# BM2Step_V1_0.net
KiCad netlist of a schematic drawn in EAGLE
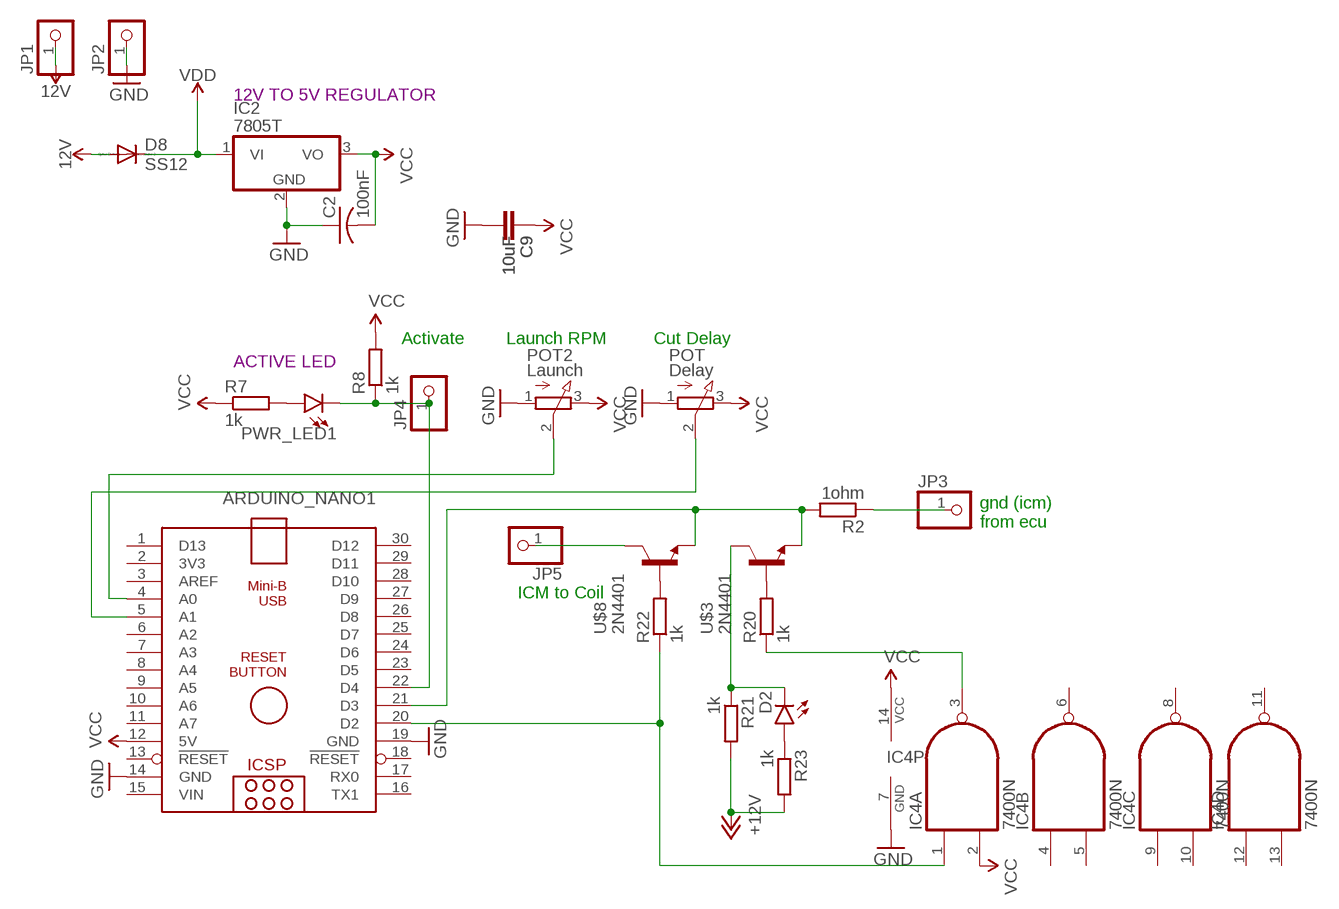
[diagram p0: schematic, sheet 1]

(export (version "E")
  (design (tool "Eeschema 10.0.6"))
  (components
    (comp (ref "ARDUINO_NANO1")
      (value "ARDUINO_NANO")
      (footprint "eagle-import:ARDUINO_NANO")
      (libsource (lib "eagle-import") (part "ARDUINO_NANO"))
    )
    (comp (ref "C2")
      (value "100nF")
      (footprint "eagle-import:C025-024X044")
      (libsource (lib "eagle-import") (part "C-US025-024X044"))
    )
    (comp (ref "C9")
      (value "10uF")
      (footprint "eagle-import:AXIAL-5MM")
      (libsource (lib "eagle-import") (part "CAP_"))
    )
    (comp (ref "D2")
      (value "LED3MM")
      (footprint "eagle-import:LED3MM")
      (libsource (lib "eagle-import") (part "led_259_LED3MM"))
    )
    (comp (ref "D8")
      (value "SS12")
      (footprint "eagle-import:D-7.5")
      (libsource (lib "eagle-import") (part "DIODE-D-7.5"))
    )
    (comp (ref "IC2")
      (value "7805T")
      (footprint "eagle-import:TO220H")
      (libsource (lib "eagle-import") (part "78T05"))
    )
    (comp (ref "IC4")
      (value "7400N")
      (footprint "eagle-import:DIL14")
      (libsource (lib "eagle-import") (part "7400N"))
    )
    (comp (ref "JP1")
      (value "PINHD-1X1_LARGE")
      (footprint "eagle-import:1X01_LARGE")
      (libsource (lib "eagle-import") (part "PINHD-1X1_LARGE"))
    )
    (comp (ref "JP2")
      (value "PINHD-1X1_LARGE")
      (footprint "eagle-import:1X01_LARGE")
      (libsource (lib "eagle-import") (part "PINHD-1X1_LARGE"))
    )
    (comp (ref "JP3")
      (value "PINHD-1X1_LARGE")
      (footprint "eagle-import:1X01_LARGE")
      (libsource (lib "eagle-import") (part "PINHD-1X1_LARGE"))
    )
    (comp (ref "JP4")
      (value "PINHD-1X1_LARGE")
      (footprint "eagle-import:1X01_LARGE")
      (libsource (lib "eagle-import") (part "PINHD-1X1_LARGE"))
    )
    (comp (ref "JP5")
      (value "PINHD-1X1_LARGE")
      (footprint "eagle-import:1X01_LARGE")
      (libsource (lib "eagle-import") (part "PINHD-1X1_LARGE"))
    )
    (comp (ref "POT")
      (value "Delay")
      (footprint "eagle-import:EVUF")
      (libsource (lib "eagle-import") (part "EVUAF2"))
    )
    (comp (ref "POT2")
      (value "Launch")
      (footprint "eagle-import:EVUF")
      (libsource (lib "eagle-import") (part "EVUAF2"))
    )
    (comp (ref "PWR_LED1")
      (value "LED3MM")
      (footprint "eagle-import:LED_3MM")
      (libsource (lib "eagle-import") (part "LED3MM"))
    )
    (comp (ref "R2")
      (value "1ohm")
      (footprint "eagle-import:0204_7")
      (libsource (lib "eagle-import") (part "R-EU_0204/7"))
    )
    (comp (ref "R7")
      (value "1k")
      (footprint "eagle-import:0204_7")
      (libsource (lib "eagle-import") (part "R-EU_0204/7"))
    )
    (comp (ref "R8")
      (value "1k")
      (footprint "eagle-import:0204_7")
      (libsource (lib "eagle-import") (part "R-EU_0204/7"))
    )
    (comp (ref "R20")
      (value "1k")
      (footprint "eagle-import:0204_7")
      (libsource (lib "eagle-import") (part "R-EU_0204/7"))
    )
    (comp (ref "R21")
      (value "1k")
      (footprint "eagle-import:0204_7")
      (libsource (lib "eagle-import") (part "R-EU_0204/7"))
    )
    (comp (ref "R22")
      (value "1k")
      (footprint "eagle-import:0204_7")
      (libsource (lib "eagle-import") (part "R-EU_0204/7"))
    )
    (comp (ref "R23")
      (value "1k")
      (footprint "eagle-import:0204_7")
      (libsource (lib "eagle-import") (part "R-EU_0204/7"))
    )
    (comp (ref "U$3")
      (value "2N4401")
      (footprint "eagle-import:TO92-ECB")
      (libsource (lib "eagle-import") (part "2SC458"))
    )
    (comp (ref "U$8")
      (value "2N4401")
      (footprint "eagle-import:TO92-ECB")
      (libsource (lib "eagle-import") (part "2SC458"))
    )
  )
  (nets
    (net (code "1") (name "+12V") (class "Default")
      (node (ref "R21") (pin "2") (pinfunction "2_2") (pintype "passive"))
      (node (ref "R23") (pin "2") (pinfunction "2_2") (pintype "passive"))
    )
    (net (code "2") (name "/VIN") (class "Default")
      (node (ref "ARDUINO_NANO1") (pin "15") (pinfunction "VIN_15") (pintype "power_in"))
    )
    (net (code "3") (name "12V") (class "Default")
      (node (ref "D8") (pin "A") (pinfunction "A_A") (pintype "passive"))
      (node (ref "JP1") (pin "1") (pinfunction "1_1") (pintype "passive"))
    )
    (net (code "4") (name "GND") (class "Default")
      (node (ref "ARDUINO_NANO1") (pin "14") (pinfunction "GND_14") (pintype "power_in"))
      (node (ref "ARDUINO_NANO1") (pin "19") (pinfunction "GND_19") (pintype "power_in"))
      (node (ref "C2") (pin "1") (pinfunction "1_1") (pintype "passive"))
      (node (ref "C9") (pin "P$2") (pinfunction "2_P$2") (pintype "passive"))
      (node (ref "IC2") (pin "2") (pinfunction "GND_2") (pintype "passive"))
      (node (ref "IC4") (pin "7") (pinfunction "GND_7") (pintype "power_in"))
      (node (ref "JP2") (pin "1") (pinfunction "1_1") (pintype "passive"))
      (node (ref "POT") (pin "1") (pinfunction "A_1") (pintype "passive"))
      (node (ref "POT2") (pin "1") (pinfunction "A_1") (pintype "passive"))
    )
    (net (code "5") (name "Net-(ARDUINO_NANO1-A0)") (class "Default")
      (node (ref "ARDUINO_NANO1") (pin "4") (pinfunction "A0_4") (pintype "bidirectional"))
      (node (ref "POT2") (pin "2") (pinfunction "S_2") (pintype "passive"))
    )
    (net (code "6") (name "Net-(ARDUINO_NANO1-A1)") (class "Default")
      (node (ref "ARDUINO_NANO1") (pin "5") (pinfunction "A1_5") (pintype "bidirectional"))
      (node (ref "POT") (pin "2") (pinfunction "S_2") (pintype "passive"))
    )
    (net (code "7") (name "Net-(ARDUINO_NANO1-D2)") (class "Default")
      (node (ref "ARDUINO_NANO1") (pin "20") (pinfunction "D2_20") (pintype "bidirectional"))
      (node (ref "IC4") (pin "1") (pinfunction "I0_1") (pintype "input"))
      (node (ref "R22") (pin "1") (pinfunction "1_1") (pintype "passive"))
    )
    (net (code "8") (name "Net-(ARDUINO_NANO1-D3)") (class "Default")
      (node (ref "ARDUINO_NANO1") (pin "21") (pinfunction "D3_21") (pintype "bidirectional"))
      (node (ref "R2") (pin "2") (pinfunction "2_2") (pintype "passive"))
      (node (ref "U$3") (pin "E") (pinfunction "E_E") (pintype "passive"))
      (node (ref "U$8") (pin "E") (pinfunction "E_E") (pintype "passive"))
    )
    (net (code "9") (name "Net-(ARDUINO_NANO1-D4)") (class "Default")
      (node (ref "ARDUINO_NANO1") (pin "22") (pinfunction "D4_22") (pintype "bidirectional"))
      (node (ref "JP4") (pin "1") (pinfunction "1_1") (pintype "passive"))
      (node (ref "PWR_LED1") (pin "K") (pinfunction "C_K") (pintype "passive"))
      (node (ref "R8") (pin "1") (pinfunction "1_1") (pintype "passive"))
    )
    (net (code "10") (name "Net-(D2-C)") (class "Default")
      (node (ref "D2") (pin "K") (pinfunction "C_K") (pintype "passive"))
      (node (ref "R21") (pin "1") (pinfunction "1_1") (pintype "passive"))
      (node (ref "U$3") (pin "C") (pinfunction "C_C") (pintype "passive"))
    )
    (net (code "11") (name "Net-(D2-PadA)") (class "Default")
      (node (ref "D2") (pin "A") (pinfunction "A_A") (pintype "passive"))
      (node (ref "R23") (pin "1") (pinfunction "1_1") (pintype "passive"))
    )
    (net (code "12") (name "Net-(IC4A-O)") (class "Default")
      (node (ref "IC4") (pin "3") (pinfunction "O_3") (pintype "output"))
      (node (ref "R20") (pin "1") (pinfunction "1_1") (pintype "passive"))
    )
    (net (code "13") (name "Net-(JP3-Pad1)") (class "Default")
      (node (ref "JP3") (pin "1") (pinfunction "1_1") (pintype "passive"))
      (node (ref "R2") (pin "1") (pinfunction "1_1") (pintype "passive"))
    )
    (net (code "14") (name "Net-(JP5-Pad1)") (class "Default")
      (node (ref "JP5") (pin "1") (pinfunction "1_1") (pintype "passive"))
      (node (ref "U$8") (pin "C") (pinfunction "C_C") (pintype "passive"))
    )
    (net (code "15") (name "Net-(PWR_LED1-PadA)") (class "Default")
      (node (ref "PWR_LED1") (pin "A") (pinfunction "A_A") (pintype "passive"))
      (node (ref "R7") (pin "2") (pinfunction "2_2") (pintype "passive"))
    )
    (net (code "16") (name "Net-(R20-Pad2)") (class "Default")
      (node (ref "R20") (pin "2") (pinfunction "2_2") (pintype "passive"))
      (node (ref "U$3") (pin "B") (pinfunction "B_B") (pintype "passive"))
    )
    (net (code "17") (name "Net-(R22-Pad2)") (class "Default")
      (node (ref "R22") (pin "2") (pinfunction "2_2") (pintype "passive"))
      (node (ref "U$8") (pin "B") (pinfunction "B_B") (pintype "passive"))
    )
    (net (code "18") (name "VCC") (class "Default")
      (node (ref "ARDUINO_NANO1") (pin "12") (pinfunction "5V_12") (pintype "power_in"))
      (node (ref "C2") (pin "2") (pinfunction "2_2") (pintype "passive"))
      (node (ref "C9") (pin "P$1") (pinfunction "1_P$1") (pintype "passive"))
      (node (ref "IC2") (pin "3") (pinfunction "VO_3") (pintype "passive"))
      (node (ref "IC4") (pin "14") (pinfunction "VCC_14") (pintype "power_in"))
      (node (ref "IC4") (pin "2") (pinfunction "I1_2") (pintype "input"))
      (node (ref "POT") (pin "3") (pinfunction "E_3") (pintype "passive"))
      (node (ref "POT2") (pin "3") (pinfunction "E_3") (pintype "passive"))
      (node (ref "R7") (pin "1") (pinfunction "1_1") (pintype "passive"))
      (node (ref "R8") (pin "2") (pinfunction "2_2") (pintype "passive"))
    )
    (net (code "19") (name "VDD") (class "Default")
      (node (ref "D8") (pin "C") (pinfunction "C_C") (pintype "passive"))
      (node (ref "IC2") (pin "1") (pinfunction "VI_1") (pintype "input"))
    )
    (net (code "20") (name "unconnected-(ARDUINO_NANO1-3V3-Pad2)") (class "Default")
      (node (ref "ARDUINO_NANO1") (pin "2") (pinfunction "3V3_2") (pintype "output"))
    )
    (net (code "21") (name "unconnected-(ARDUINO_NANO1-A2-Pad6)") (class "Default")
      (node (ref "ARDUINO_NANO1") (pin "6") (pinfunction "A2_6") (pintype "bidirectional"))
    )
    (net (code "22") (name "unconnected-(ARDUINO_NANO1-A3-Pad7)") (class "Default")
      (node (ref "ARDUINO_NANO1") (pin "7") (pinfunction "A3_7") (pintype "bidirectional"))
    )
    (net (code "23") (name "unconnected-(ARDUINO_NANO1-A4-Pad8)") (class "Default")
      (node (ref "ARDUINO_NANO1") (pin "8") (pinfunction "A4_8") (pintype "bidirectional"))
    )
    (net (code "24") (name "unconnected-(ARDUINO_NANO1-A5-Pad9)") (class "Default")
      (node (ref "ARDUINO_NANO1") (pin "9") (pinfunction "A5_9") (pintype "bidirectional"))
    )
    (net (code "25") (name "unconnected-(ARDUINO_NANO1-A6-Pad10)") (class "Default")
      (node (ref "ARDUINO_NANO1") (pin "10") (pinfunction "A6_10") (pintype "bidirectional"))
    )
    (net (code "26") (name "unconnected-(ARDUINO_NANO1-A7-Pad11)") (class "Default")
      (node (ref "ARDUINO_NANO1") (pin "11") (pinfunction "A7_11") (pintype "bidirectional"))
    )
    (net (code "27") (name "unconnected-(ARDUINO_NANO1-AREF-Pad3)") (class "Default")
      (node (ref "ARDUINO_NANO1") (pin "3") (pinfunction "AREF_3") (pintype "input"))
    )
    (net (code "28") (name "unconnected-(ARDUINO_NANO1-D5-Pad23)") (class "Default")
      (node (ref "ARDUINO_NANO1") (pin "23") (pinfunction "D5_23") (pintype "bidirectional"))
    )
    (net (code "29") (name "unconnected-(ARDUINO_NANO1-D6-Pad24)") (class "Default")
      (node (ref "ARDUINO_NANO1") (pin "24") (pinfunction "D6_24") (pintype "bidirectional"))
    )
    (net (code "30") (name "unconnected-(ARDUINO_NANO1-D7-Pad25)") (class "Default")
      (node (ref "ARDUINO_NANO1") (pin "25") (pinfunction "D7_25") (pintype "bidirectional"))
    )
    (net (code "31") (name "unconnected-(ARDUINO_NANO1-D8-Pad26)") (class "Default")
      (node (ref "ARDUINO_NANO1") (pin "26") (pinfunction "D8_26") (pintype "bidirectional"))
    )
    (net (code "32") (name "unconnected-(ARDUINO_NANO1-D9-Pad27)") (class "Default")
      (node (ref "ARDUINO_NANO1") (pin "27") (pinfunction "D9_27") (pintype "bidirectional"))
    )
    (net (code "33") (name "unconnected-(ARDUINO_NANO1-D10-Pad28)") (class "Default")
      (node (ref "ARDUINO_NANO1") (pin "28") (pinfunction "D10_28") (pintype "bidirectional"))
    )
    (net (code "34") (name "unconnected-(ARDUINO_NANO1-D11-Pad29)") (class "Default")
      (node (ref "ARDUINO_NANO1") (pin "29") (pinfunction "D11_29") (pintype "bidirectional"))
    )
    (net (code "35") (name "unconnected-(ARDUINO_NANO1-D12-Pad30)") (class "Default")
      (node (ref "ARDUINO_NANO1") (pin "30") (pinfunction "D12_30") (pintype "bidirectional"))
    )
    (net (code "36") (name "unconnected-(ARDUINO_NANO1-D13-Pad1)") (class "Default")
      (node (ref "ARDUINO_NANO1") (pin "1") (pinfunction "D13_1") (pintype "bidirectional"))
    )
    (net (code "37") (name "unconnected-(ARDUINO_NANO1-RX0-Pad17)") (class "Default")
      (node (ref "ARDUINO_NANO1") (pin "17") (pinfunction "RX0_17") (pintype "bidirectional"))
    )
    (net (code "38") (name "unconnected-(ARDUINO_NANO1-TX1-Pad16)") (class "Default")
      (node (ref "ARDUINO_NANO1") (pin "16") (pinfunction "TX1_16") (pintype "bidirectional"))
    )
    (net (code "39") (name "unconnected-(ARDUINO_NANO1-~{RESET}-Pad13)") (class "Default")
      (node (ref "ARDUINO_NANO1") (pin "13") (pinfunction "~{RESET}_13") (pintype "input"))
    )
    (net (code "40") (name "unconnected-(ARDUINO_NANO1-~{RESET}-Pad18)") (class "Default")
      (node (ref "ARDUINO_NANO1") (pin "18") (pinfunction "~{RESET}_18") (pintype "input"))
    )
    (net (code "41") (name "unconnected-(IC4B-I0-Pad4)") (class "Default")
      (node (ref "IC4") (pin "4") (pinfunction "I0_4") (pintype "input"))
    )
    (net (code "42") (name "unconnected-(IC4B-I1-Pad5)") (class "Default")
      (node (ref "IC4") (pin "5") (pinfunction "I1_5") (pintype "input"))
    )
    (net (code "43") (name "unconnected-(IC4B-O-Pad6)") (class "Default")
      (node (ref "IC4") (pin "6") (pinfunction "O_6") (pintype "output"))
    )
    (net (code "44") (name "unconnected-(IC4C-I0-Pad9)") (class "Default")
      (node (ref "IC4") (pin "9") (pinfunction "I0_9") (pintype "input"))
    )
    (net (code "45") (name "unconnected-(IC4C-I1-Pad10)") (class "Default")
      (node (ref "IC4") (pin "10") (pinfunction "I1_10") (pintype "input"))
    )
    (net (code "46") (name "unconnected-(IC4C-O-Pad8)") (class "Default")
      (node (ref "IC4") (pin "8") (pinfunction "O_8") (pintype "output"))
    )
    (net (code "47") (name "unconnected-(IC4D-I0-Pad12)") (class "Default")
      (node (ref "IC4") (pin "12") (pinfunction "I0_12") (pintype "input"))
    )
    (net (code "48") (name "unconnected-(IC4D-I1-Pad13)") (class "Default")
      (node (ref "IC4") (pin "13") (pinfunction "I1_13") (pintype "input"))
    )
    (net (code "49") (name "unconnected-(IC4D-O-Pad11)") (class "Default")
      (node (ref "IC4") (pin "11") (pinfunction "O_11") (pintype "output"))
    )
  )
)
